# PSU.net
KiCad netlist of a schematic drawn in Altium Designer
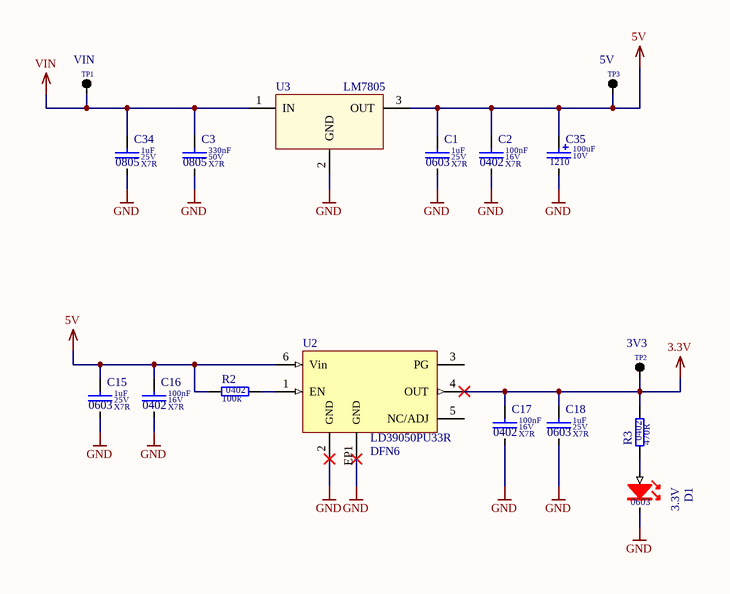
[diagram p0: PSU.SchDoc]

(export (version "E")
  (design (tool "Eeschema 10.0.6"))
  (components
    (comp (ref "C1")
      (value "1uF")
      (footprint "C_0603_1608")
      (description "Capacitor")
      (fields
        (field (name "DIELECTRIC") "X7R")
        (field (name "VOLTAGE") "25V")
        (field (name "SCH_FOOTPRINT") "0603")
        (field (name "PART NUMBER") "C_1uF_25V_X7R_0603_10")
        (field (name "MANUFACTURER") "Samsung")
      )
      (libsource (lib "Library") (part "C"))
    )
    (comp (ref "C2")
      (value "100nF")
      (footprint "C_0402_1005")
      (description "Capacitor")
      (fields
        (field (name "DIELECTRIC") "X7R")
        (field (name "VOLTAGE") "16V")
        (field (name "SCH_FOOTPRINT") "0402")
        (field (name "PART NUMBER") "C_100nF_16V_X7R_0402_10")
        (field (name "MANUFACTURER") "Murata")
      )
      (libsource (lib "Library") (part "C"))
    )
    (comp (ref "C3")
      (value "330nF")
      (footprint "C_0805_2012")
      (description "Capacitor")
      (fields
        (field (name "DIELECTRIC") "X7R")
        (field (name "VOLTAGE") "50V")
        (field (name "SCH_FOOTPRINT") "0805")
        (field (name "PART NUMBER") "C_2.2uF_25V_X7R_0805_10")
        (field (name "MANUFACTURER") "Murata")
      )
      (libsource (lib "Library") (part "C"))
    )
    (comp (ref "C15")
      (value "1uF")
      (footprint "C_0603_1608")
      (description "Capacitor")
      (fields
        (field (name "DIELECTRIC") "X7R")
        (field (name "VOLTAGE") "25V")
        (field (name "SCH_FOOTPRINT") "0603")
        (field (name "PART NUMBER") "C_1uF_25V_X7R_0603_10")
        (field (name "MANUFACTURER") "Samsung")
      )
      (libsource (lib "Library") (part "C"))
    )
    (comp (ref "C16")
      (value "100nF")
      (footprint "C_0402_1005")
      (description "Capacitor")
      (fields
        (field (name "DIELECTRIC") "X7R")
        (field (name "VOLTAGE") "16V")
        (field (name "SCH_FOOTPRINT") "0402")
        (field (name "PART NUMBER") "C_100nF_16V_X7R_0402_10")
        (field (name "MANUFACTURER") "Murata")
      )
      (libsource (lib "Library") (part "C"))
    )
    (comp (ref "C17")
      (value "100nF")
      (footprint "C_0402_1005")
      (description "Capacitor")
      (fields
        (field (name "DIELECTRIC") "X7R")
        (field (name "VOLTAGE") "16V")
        (field (name "SCH_FOOTPRINT") "0402")
        (field (name "PART NUMBER") "C_100nF_16V_X7R_0402_10")
        (field (name "MANUFACTURER") "Murata")
      )
      (libsource (lib "Library") (part "C"))
    )
    (comp (ref "C18")
      (value "1uF")
      (footprint "C_0603_1608")
      (description "Capacitor")
      (fields
        (field (name "DIELECTRIC") "X7R")
        (field (name "VOLTAGE") "25V")
        (field (name "SCH_FOOTPRINT") "0603")
        (field (name "PART NUMBER") "C_1uF_25V_X7R_0603_10")
        (field (name "MANUFACTURER") "Samsung")
      )
      (libsource (lib "Library") (part "C"))
    )
    (comp (ref "C34")
      (value "1uF")
      (footprint "C_0805_2012")
      (description "Capacitor")
      (fields
        (field (name "DIELECTRIC") "X7R")
        (field (name "VOLTAGE") "25V")
        (field (name "SCH_FOOTPRINT") "0805")
        (field (name "PART NUMBER") "C_2.2uF_25V_X7R_0805_10")
        (field (name "MANUFACTURER") "Murata")
      )
      (libsource (lib "Library") (part "C"))
    )
    (comp (ref "C35")
      (value "100uF")
      (footprint "CT_1210_3225")
      (description "Capacitor")
      (fields
        (field (name "SCH_FOOTPRINT") "1210")
        (field (name "VOLTAGE") "10V")
        (field (name "PART NUMBER") "CT_100uF_10V_TA2O5_1210_20")
        (field (name "MANUFACTURER") "AVX")
      )
      (libsource (lib "Library") (part "CT"))
    )
    (comp (ref "D1")
      (value "3.3V")
      (footprint "OL_0603_1608")
      (description "LED_RED")
      (fields
        (field (name "SCH_FOOTPRINT") "0603")
        (field (name "PART NUMBER") "OL_R_0603")
        (field (name "MANUFACTURER") "Lite-On")
      )
      (libsource (lib "Library") (part "OL_R"))
    )
    (comp (ref "R2")
      (value "100k")
      (footprint "R_0402_1005")
      (fields
        (field (name "SCH_FOOTPRINT") "0402")
        (field (name "PART NUMBER") "R_100k_0402_1")
        (field (name "VOLTAGE") "50V")
        (field (name "POWER") "63mW")
      )
      (libsource (lib "Library") (part "R"))
    )
    (comp (ref "R3")
      (value "470R")
      (footprint "R_0402_1005")
      (fields
        (field (name "SCH_FOOTPRINT") "0402")
        (field (name "PART NUMBER") "R_470R_0402_1")
        (field (name "VOLTAGE") "50V")
        (field (name "POWER") "63mW")
      )
      (libsource (lib "Library") (part "R"))
    )
    (comp (ref "TP1")
      (value "VIN")
      (footprint "TP_PAD")
      (description "Testpoint")
      (fields (field (name "PART NUMBER") "TP_PAD"))
      (libsource (lib "Library") (part "TP_TESTPOINT"))
    )
    (comp (ref "TP2")
      (value "3V3")
      (footprint "TP_PAD")
      (description "Testpoint")
      (fields (field (name "PART NUMBER") "TP_PAD"))
      (libsource (lib "Library") (part "TP_TESTPOINT"))
    )
    (comp (ref "TP3")
      (value "5V")
      (footprint "TP_PAD")
      (description "Testpoint")
      (fields (field (name "PART NUMBER") "TP_PAD"))
      (libsource (lib "Library") (part "TP_TESTPOINT"))
    )
    (comp (ref "U2")
      (value "LD39050PU33R")
      (footprint "DFN6_3x3")
      (fields
        (field (name "SCH_FOOTPRINT") "DFN6")
        (field (name "PART NUMBER") "VL_LD39050PU33R")
        (field (name "VOLTAGE") "3.3V")
        (field (name "MANUFACTURER") "STMicroelectronics")
      )
      (libsource (lib "Library") (part "VL_LD39050"))
    )
    (comp (ref "U3")
      (value "LM7805")
      (footprint "LM7805")
      (description "linear voltage stabilizer")
      (libsource (lib "soldering_station") (part "LM7805"))
    )
  )
  (nets
    (net (code "1") (name "3.3V") (class "Default")
      (node (ref "C17") (pin "1") (pinfunction "1_1") (pintype "passive"))
      (node (ref "C18") (pin "1") (pinfunction "1_1") (pintype "passive"))
      (node (ref "R3") (pin "2") (pinfunction "2_2") (pintype "passive"))
      (node (ref "TP2") (pin "1") (pinfunction "TP_1") (pintype "passive"))
      (node (ref "U2") (pin "4") (pinfunction "OUT_4") (pintype "output"))
    )
    (net (code "2") (name "5V") (class "Default")
      (node (ref "C1") (pin "1") (pinfunction "1_1") (pintype "passive"))
      (node (ref "C15") (pin "1") (pinfunction "1_1") (pintype "passive"))
      (node (ref "C16") (pin "1") (pinfunction "1_1") (pintype "passive"))
      (node (ref "C2") (pin "1") (pinfunction "1_1") (pintype "passive"))
      (node (ref "C35") (pin "1") (pinfunction "1_1") (pintype "passive"))
      (node (ref "R2") (pin "1") (pinfunction "1_1") (pintype "passive"))
      (node (ref "TP3") (pin "1") (pinfunction "TP_1") (pintype "passive"))
      (node (ref "U2") (pin "6") (pinfunction "Vin_6") (pintype "input"))
      (node (ref "U3") (pin "3") (pinfunction "OUT_3") (pintype "power_in"))
    )
    (net (code "3") (name "GND") (class "Default")
      (node (ref "C1") (pin "2") (pinfunction "2_2") (pintype "passive"))
      (node (ref "C15") (pin "2") (pinfunction "2_2") (pintype "passive"))
      (node (ref "C16") (pin "2") (pinfunction "2_2") (pintype "passive"))
      (node (ref "C17") (pin "2") (pinfunction "2_2") (pintype "passive"))
      (node (ref "C18") (pin "2") (pinfunction "2_2") (pintype "passive"))
      (node (ref "C2") (pin "2") (pinfunction "2_2") (pintype "passive"))
      (node (ref "C3") (pin "2") (pinfunction "2_2") (pintype "passive"))
      (node (ref "C34") (pin "2") (pinfunction "2_2") (pintype "passive"))
      (node (ref "C35") (pin "2") (pinfunction "2_2") (pintype "passive"))
      (node (ref "D1") (pin "1") (pinfunction "K_1") (pintype "output"))
      (node (ref "U2") (pin "2") (pinfunction "GND_2") (pintype "power_in"))
      (node (ref "U2") (pin "EP1") (pinfunction "GND_EP1") (pintype "power_in"))
      (node (ref "U3") (pin "2") (pinfunction "GND_2") (pintype "power_in"))
    )
    (net (code "4") (name "Net-(D1-A)") (class "Default")
      (node (ref "D1") (pin "2") (pinfunction "A_2") (pintype "input"))
      (node (ref "R3") (pin "1") (pinfunction "1_1") (pintype "passive"))
    )
    (net (code "5") (name "Net-(U2-EN)") (class "Default")
      (node (ref "R2") (pin "2") (pinfunction "2_2") (pintype "passive"))
      (node (ref "U2") (pin "1") (pinfunction "EN_1") (pintype "input"))
    )
    (net (code "6") (name "VIN") (class "Default")
      (node (ref "C3") (pin "1") (pinfunction "1_1") (pintype "passive"))
      (node (ref "C34") (pin "1") (pinfunction "1_1") (pintype "passive"))
      (node (ref "TP1") (pin "1") (pinfunction "TP_1") (pintype "passive"))
      (node (ref "U3") (pin "1") (pinfunction "IN_1") (pintype "power_in"))
    )
    (net (code "7") (name "unconnected-(U2-NC{slash}ADJ-Pad5)") (class "Default")
      (node (ref "U2") (pin "5") (pinfunction "NC/ADJ_5") (pintype "passive"))
    )
    (net (code "8") (name "unconnected-(U2-PG-Pad3)") (class "Default")
      (node (ref "U2") (pin "3") (pinfunction "PG_3") (pintype "passive"))
    )
  )
)
